# CT310_H_V1_0.net
KiCad netlist of a schematic drawn in Altium Designer
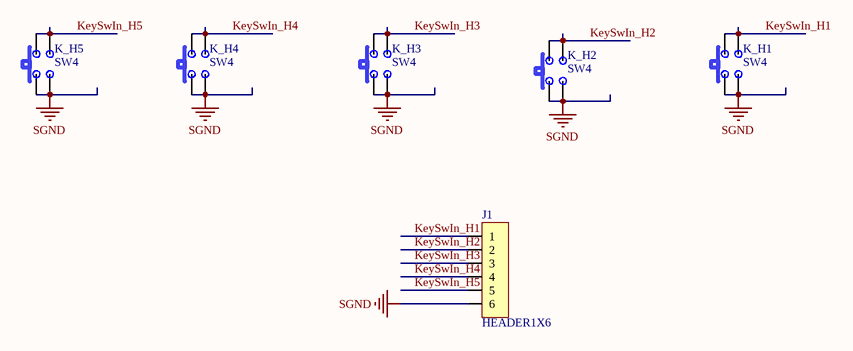
[diagram p0: CT310高端控制盒H区按键电路V1.0.SchDoc]

(export (version "E")
  (design (tool "Eeschema 10.0.6"))
  (components
    (comp (ref "J1")
      (value "HEADER1X6")
      (footprint "ZH1X6WT-1.5")
      (libsource (lib "Connector Class") (part "HEADER1X6"))
    )
    (comp (ref "K_H1")
      (value "SW4")
      (footprint "SW-MEC")
      (libsource (lib "Passive Components Class") (part "SW-key"))
    )
    (comp (ref "K_H2")
      (value "SW4")
      (footprint "SW-MEC")
      (libsource (lib "Passive Components Class") (part "SW-key"))
    )
    (comp (ref "K_H3")
      (value "SW4")
      (footprint "SW-MEC")
      (libsource (lib "Passive Components Class") (part "SW-key"))
    )
    (comp (ref "K_H4")
      (value "SW4")
      (footprint "SW-MEC")
      (libsource (lib "Passive Components Class") (part "SW-key"))
    )
    (comp (ref "K_H5")
      (value "SW4")
      (footprint "SW-MEC")
      (libsource (lib "Passive Components Class") (part "SW-key"))
    )
  )
  (nets
    (net (code "1") (name "/KeySwIn_H1") (class "Default")
      (node (ref "J1") (pin "1") (pinfunction "1_1") (pintype "passive"))
      (node (ref "K_H1") (pin "2") (pinfunction "2_2") (pintype "passive"))
    )
    (net (code "2") (name "/KeySwIn_H2") (class "Default")
      (node (ref "J1") (pin "2") (pinfunction "2_2") (pintype "passive"))
      (node (ref "K_H2") (pin "2") (pinfunction "2_2") (pintype "passive"))
    )
    (net (code "3") (name "/KeySwIn_H3") (class "Default")
      (node (ref "J1") (pin "3") (pinfunction "3_3") (pintype "passive"))
      (node (ref "K_H3") (pin "2") (pinfunction "2_2") (pintype "passive"))
    )
    (net (code "4") (name "/KeySwIn_H4") (class "Default")
      (node (ref "J1") (pin "4") (pinfunction "4_4") (pintype "passive"))
      (node (ref "K_H4") (pin "2") (pinfunction "2_2") (pintype "passive"))
    )
    (net (code "5") (name "/KeySwIn_H5") (class "Default")
      (node (ref "J1") (pin "5") (pinfunction "5_5") (pintype "passive"))
      (node (ref "K_H5") (pin "2") (pinfunction "2_2") (pintype "passive"))
    )
    (net (code "6") (name "SGND") (class "Default")
      (node (ref "J1") (pin "6") (pinfunction "6_6") (pintype "passive"))
      (node (ref "K_H1") (pin "1") (pinfunction "1_1") (pintype "passive"))
      (node (ref "K_H2") (pin "1") (pinfunction "1_1") (pintype "passive"))
      (node (ref "K_H3") (pin "1") (pinfunction "1_1") (pintype "passive"))
      (node (ref "K_H4") (pin "1") (pinfunction "1_1") (pintype "passive"))
      (node (ref "K_H5") (pin "1") (pinfunction "1_1") (pintype "passive"))
    )
  )
)
